# Harness_Wrapper.net
KiCad netlist of a schematic drawn in Altium Designer
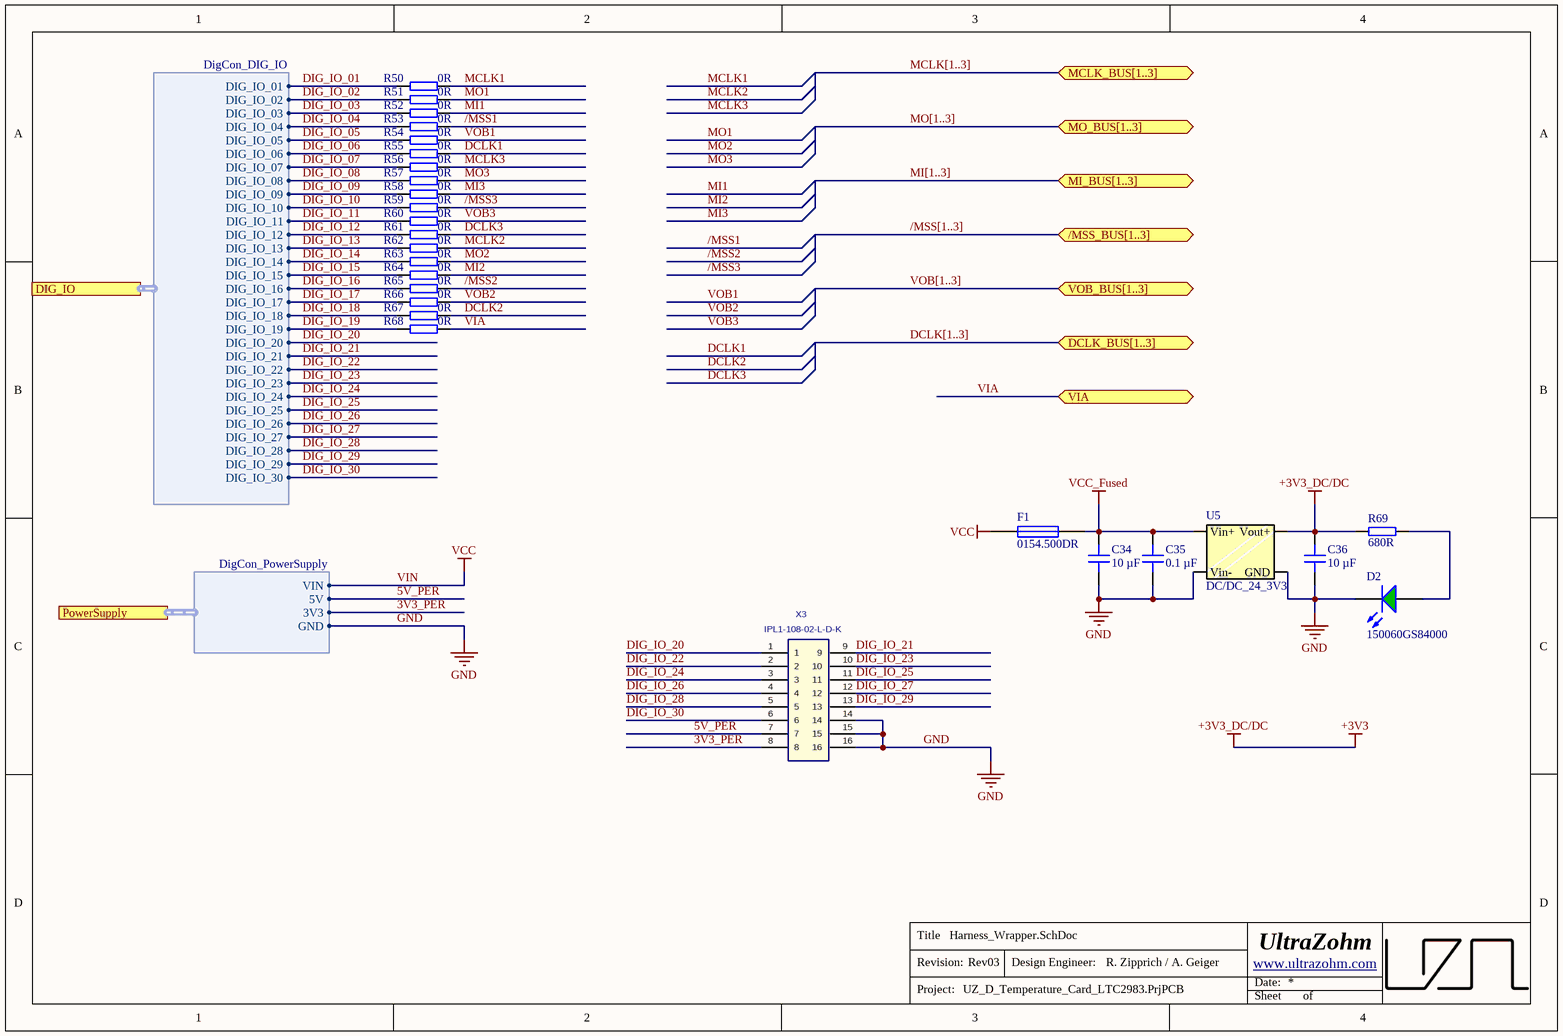
[diagram p0: Harness_Wrapper.SchDoc]

(export (version "E")
  (design (tool "Eeschema 10.0.6"))
  (components
    (comp (ref "C34")
      (value "10 µF")
      (footprint "C_0603")
      (description "Capacitor 0603, 6.3 VDC, 10 µF, X5R")
      (fields
        (field (name "MANUFACTURER PART NUMBER") "GRM185R60J106ME15D")
        (field (name "MANUFACTURER") "muRata")
        (field (name "CREATED FROM") "MGremer")
      )
      (libsource (lib "user") (part "Capacitor"))
    )
    (comp (ref "C35")
      (value "0.1 µF")
      (footprint "C_0603")
      (description "Capacitor 0603, 50 VDC, 0.1 µF, X7R")
      (fields
        (field (name "MANUFACTURER PART NUMBER") "C0603X104K5RAC7411")
        (field (name "MANUFACTURER") "KEMET")
        (field (name "CREATED FROM") "MGremer")
      )
      (libsource (lib "user") (part "Capacitor"))
    )
    (comp (ref "C36")
      (value "10 µF")
      (footprint "C_0603")
      (description "Capacitor 0603, 6.3 VDC, 10 µF, X5R")
      (fields
        (field (name "MANUFACTURER PART NUMBER") "GRM185R60J106ME15D")
        (field (name "MANUFACTURER") "muRata")
        (field (name "CREATED FROM") "MGremer")
      )
      (libsource (lib "user") (part "Capacitor"))
    )
    (comp (ref "D2")
      (value "150060GS84000")
      (footprint "WL-SMCW_0603")
      (description "WL-SMCW SMD Mono-color Chip LED Waterclear Green")
      (fields
        (field (name "MANUFACTURER") "Wuerth Elektronik")
        (field (name "LCSC PART NUMBER") "C72043")
        (field (name "CREATED FROM") "MGremer")
      )
      (libsource (lib "user") (part "LED_Green"))
    )
    (comp (ref "F1")
      (value "0154.500DR")
      (footprint "Littlefuse_154")
      (description "Fuse OMNI BLOK 154")
      (fields
        (field (name "MANUFACTURER") "Littlefuse")
        (field (name "LCSC PART NUMBER") "C720204")
        (field (name "CREATED FROM") "MGremer")
      )
      (libsource (lib "user") (part "Fuse Littelfuse 154 Fuse"))
    )
    (comp (ref "R50")
      (value "0R")
      (footprint "RES 0603_1608")
      (description "SMD resistor E24 series")
      (fields
        (field (name "MANUFACTURER PART NUMBER") "RC0603JR-070RL")
        (field (name "MANUFACTURER") "YAGEO")
        (field (name "CREATED FROM") "MGremer")
      )
      (libsource (lib "user") (part "Resistor"))
    )
    (comp (ref "R51")
      (value "0R")
      (footprint "RES 0603_1608")
      (description "SMD resistor E24 series")
      (fields
        (field (name "MANUFACTURER PART NUMBER") "RC0603JR-070RL")
        (field (name "MANUFACTURER") "YAGEO")
        (field (name "CREATED FROM") "MGremer")
      )
      (libsource (lib "user") (part "Resistor"))
    )
    (comp (ref "R52")
      (value "0R")
      (footprint "RES 0603_1608")
      (description "SMD resistor E24 series")
      (fields
        (field (name "MANUFACTURER PART NUMBER") "RC0603JR-070RL")
        (field (name "MANUFACTURER") "YAGEO")
        (field (name "CREATED FROM") "MGremer")
      )
      (libsource (lib "user") (part "Resistor"))
    )
    (comp (ref "R53")
      (value "0R")
      (footprint "RES 0603_1608")
      (description "SMD resistor E24 series")
      (fields
        (field (name "MANUFACTURER PART NUMBER") "RC0603JR-070RL")
        (field (name "MANUFACTURER") "YAGEO")
        (field (name "CREATED FROM") "MGremer")
      )
      (libsource (lib "user") (part "Resistor"))
    )
    (comp (ref "R54")
      (value "0R")
      (footprint "RES 0603_1608")
      (description "SMD resistor E24 series")
      (fields
        (field (name "MANUFACTURER PART NUMBER") "RC0603JR-070RL")
        (field (name "MANUFACTURER") "YAGEO")
        (field (name "CREATED FROM") "MGremer")
      )
      (libsource (lib "user") (part "Resistor"))
    )
    (comp (ref "R55")
      (value "0R")
      (footprint "RES 0603_1608")
      (description "SMD resistor E24 series")
      (fields
        (field (name "MANUFACTURER PART NUMBER") "RC0603JR-070RL")
        (field (name "MANUFACTURER") "YAGEO")
        (field (name "CREATED FROM") "MGremer")
      )
      (libsource (lib "user") (part "Resistor"))
    )
    (comp (ref "R56")
      (value "0R")
      (footprint "RES 0603_1608")
      (description "SMD resistor E24 series")
      (fields
        (field (name "MANUFACTURER PART NUMBER") "RC0603JR-070RL")
        (field (name "MANUFACTURER") "YAGEO")
        (field (name "CREATED FROM") "MGremer")
      )
      (libsource (lib "user") (part "Resistor"))
    )
    (comp (ref "R57")
      (value "0R")
      (footprint "RES 0603_1608")
      (description "SMD resistor E24 series")
      (fields
        (field (name "MANUFACTURER PART NUMBER") "RC0603JR-070RL")
        (field (name "MANUFACTURER") "YAGEO")
        (field (name "CREATED FROM") "MGremer")
      )
      (libsource (lib "user") (part "Resistor"))
    )
    (comp (ref "R58")
      (value "0R")
      (footprint "RES 0603_1608")
      (description "SMD resistor E24 series")
      (fields
        (field (name "MANUFACTURER PART NUMBER") "RC0603JR-070RL")
        (field (name "MANUFACTURER") "YAGEO")
        (field (name "CREATED FROM") "MGremer")
      )
      (libsource (lib "user") (part "Resistor"))
    )
    (comp (ref "R59")
      (value "0R")
      (footprint "RES 0603_1608")
      (description "SMD resistor E24 series")
      (fields
        (field (name "MANUFACTURER PART NUMBER") "RC0603JR-070RL")
        (field (name "MANUFACTURER") "YAGEO")
        (field (name "CREATED FROM") "MGremer")
      )
      (libsource (lib "user") (part "Resistor"))
    )
    (comp (ref "R60")
      (value "0R")
      (footprint "RES 0603_1608")
      (description "SMD resistor E24 series")
      (fields
        (field (name "MANUFACTURER PART NUMBER") "RC0603JR-070RL")
        (field (name "MANUFACTURER") "YAGEO")
        (field (name "CREATED FROM") "MGremer")
      )
      (libsource (lib "user") (part "Resistor"))
    )
    (comp (ref "R61")
      (value "0R")
      (footprint "RES 0603_1608")
      (description "SMD resistor E24 series")
      (fields
        (field (name "MANUFACTURER PART NUMBER") "RC0603JR-070RL")
        (field (name "MANUFACTURER") "YAGEO")
        (field (name "CREATED FROM") "MGremer")
      )
      (libsource (lib "user") (part "Resistor"))
    )
    (comp (ref "R62")
      (value "0R")
      (footprint "RES 0603_1608")
      (description "SMD resistor E24 series")
      (fields
        (field (name "MANUFACTURER PART NUMBER") "RC0603JR-070RL")
        (field (name "MANUFACTURER") "YAGEO")
        (field (name "CREATED FROM") "MGremer")
      )
      (libsource (lib "user") (part "Resistor"))
    )
    (comp (ref "R63")
      (value "0R")
      (footprint "RES 0603_1608")
      (description "SMD resistor E24 series")
      (fields
        (field (name "MANUFACTURER PART NUMBER") "RC0603JR-070RL")
        (field (name "MANUFACTURER") "YAGEO")
        (field (name "CREATED FROM") "MGremer")
      )
      (libsource (lib "user") (part "Resistor"))
    )
    (comp (ref "R64")
      (value "0R")
      (footprint "RES 0603_1608")
      (description "SMD resistor E24 series")
      (fields
        (field (name "MANUFACTURER PART NUMBER") "RC0603JR-070RL")
        (field (name "MANUFACTURER") "YAGEO")
        (field (name "CREATED FROM") "MGremer")
      )
      (libsource (lib "user") (part "Resistor"))
    )
    (comp (ref "R65")
      (value "0R")
      (footprint "RES 0603_1608")
      (description "SMD resistor E24 series")
      (fields
        (field (name "MANUFACTURER PART NUMBER") "RC0603JR-070RL")
        (field (name "MANUFACTURER") "YAGEO")
        (field (name "CREATED FROM") "MGremer")
      )
      (libsource (lib "user") (part "Resistor"))
    )
    (comp (ref "R66")
      (value "0R")
      (footprint "RES 0603_1608")
      (description "SMD resistor E24 series")
      (fields
        (field (name "MANUFACTURER PART NUMBER") "RC0603JR-070RL")
        (field (name "MANUFACTURER") "YAGEO")
        (field (name "CREATED FROM") "MGremer")
      )
      (libsource (lib "user") (part "Resistor"))
    )
    (comp (ref "R67")
      (value "0R")
      (footprint "RES 0603_1608")
      (description "SMD resistor E24 series")
      (fields
        (field (name "MANUFACTURER PART NUMBER") "RC0603JR-070RL")
        (field (name "MANUFACTURER") "YAGEO")
        (field (name "CREATED FROM") "MGremer")
      )
      (libsource (lib "user") (part "Resistor"))
    )
    (comp (ref "R68")
      (value "0R")
      (footprint "RES 0603_1608")
      (description "SMD resistor E24 series")
      (fields
        (field (name "MANUFACTURER PART NUMBER") "RC0603JR-070RL")
        (field (name "MANUFACTURER") "YAGEO")
        (field (name "CREATED FROM") "MGremer")
      )
      (libsource (lib "user") (part "Resistor"))
    )
    (comp (ref "R69")
      (value "680R")
      (footprint "RES 0603_1608")
      (description "SMD resistor E24 series")
      (fields
        (field (name "MANUFACTURER PART NUMBER") "RK73B1JTTDD681J")
        (field (name "MANUFACTURER") "KOA Speer")
        (field (name "CREATED FROM") "MGremer")
      )
      (libsource (lib "user") (part "Resistor"))
    )
    (comp (ref "U5")
      (value "DC/DC_24_3V3")
      (footprint "SIP4DCDC")
      (fields (field (name "LCSC PART NUMBER") "C7500913"))
      (libsource (lib "PRJ_LIB_LTC2983_Card") (part "DC/DC_Single"))
    )
    (comp (ref "X3")
      (value "IPL1-108-02-L-D-K")
      (footprint "IPL1-108-02-L-D-K")
      (description "2.54 mm Double Row Termin Assembly (SMD)")
      (fields (field (name "MANUFACTURER") "SAMTEC") (field (name "CREATED FROM") "MGremer"))
      (libsource (lib "user") (part "IPL1-108-XX-X-D-X"))
    )
  )
  (nets
    (net (code "6") (name "+3V3") (class "Default")
      (node (ref "C36") (pin "2") (pinfunction "2_2") (pintype "passive"))
      (node (ref "R69") (pin "1") (pinfunction "1_1") (pintype "passive"))
      (node (ref "U5") (pin "6") (pinfunction "Vout+_6") (pintype "passive"))
    )
    (net (code "7") (name "/3V3_PER") (class "Default")
      (node (ref "X3") (pin "8") (pinfunction "8_8") (pintype "passive"))
    )
    (net (code "8") (name "/5V_PER") (class "Default")
      (node (ref "X3") (pin "7") (pinfunction "7_7") (pintype "passive"))
    )
    (net (code "9") (name "/DCLK1") (class "Default")
      (node (ref "R55") (pin "2") (pinfunction "2_2") (pintype "passive"))
    )
    (net (code "10") (name "/DCLK2") (class "Default")
      (node (ref "R67") (pin "2") (pinfunction "2_2") (pintype "passive"))
    )
    (net (code "11") (name "/DCLK3") (class "Default")
      (node (ref "R61") (pin "2") (pinfunction "2_2") (pintype "passive"))
    )
    (net (code "13") (name "/DIG_IO_01") (class "Default")
      (node (ref "R50") (pin "1") (pinfunction "1_1") (pintype "passive"))
    )
    (net (code "14") (name "/DIG_IO_02") (class "Default")
      (node (ref "R51") (pin "1") (pinfunction "1_1") (pintype "passive"))
    )
    (net (code "15") (name "/DIG_IO_03") (class "Default")
      (node (ref "R52") (pin "1") (pinfunction "1_1") (pintype "passive"))
    )
    (net (code "16") (name "/DIG_IO_04") (class "Default")
      (node (ref "R53") (pin "1") (pinfunction "1_1") (pintype "passive"))
    )
    (net (code "17") (name "/DIG_IO_05") (class "Default")
      (node (ref "R54") (pin "1") (pinfunction "1_1") (pintype "passive"))
    )
    (net (code "18") (name "/DIG_IO_06") (class "Default")
      (node (ref "R55") (pin "1") (pinfunction "1_1") (pintype "passive"))
    )
    (net (code "19") (name "/DIG_IO_07") (class "Default")
      (node (ref "R56") (pin "1") (pinfunction "1_1") (pintype "passive"))
    )
    (net (code "20") (name "/DIG_IO_08") (class "Default")
      (node (ref "R57") (pin "1") (pinfunction "1_1") (pintype "passive"))
    )
    (net (code "21") (name "/DIG_IO_09") (class "Default")
      (node (ref "R58") (pin "1") (pinfunction "1_1") (pintype "passive"))
    )
    (net (code "22") (name "/DIG_IO_10") (class "Default")
      (node (ref "R59") (pin "1") (pinfunction "1_1") (pintype "passive"))
    )
    (net (code "23") (name "/DIG_IO_11") (class "Default")
      (node (ref "R60") (pin "1") (pinfunction "1_1") (pintype "passive"))
    )
    (net (code "24") (name "/DIG_IO_12") (class "Default")
      (node (ref "R61") (pin "1") (pinfunction "1_1") (pintype "passive"))
    )
    (net (code "25") (name "/DIG_IO_13") (class "Default")
      (node (ref "R62") (pin "1") (pinfunction "1_1") (pintype "passive"))
    )
    (net (code "26") (name "/DIG_IO_14") (class "Default")
      (node (ref "R63") (pin "1") (pinfunction "1_1") (pintype "passive"))
    )
    (net (code "27") (name "/DIG_IO_15") (class "Default")
      (node (ref "R64") (pin "1") (pinfunction "1_1") (pintype "passive"))
    )
    (net (code "28") (name "/DIG_IO_16") (class "Default")
      (node (ref "R65") (pin "1") (pinfunction "1_1") (pintype "passive"))
    )
    (net (code "29") (name "/DIG_IO_17") (class "Default")
      (node (ref "R66") (pin "1") (pinfunction "1_1") (pintype "passive"))
    )
    (net (code "30") (name "/DIG_IO_18") (class "Default")
      (node (ref "R67") (pin "1") (pinfunction "1_1") (pintype "passive"))
    )
    (net (code "31") (name "/DIG_IO_19") (class "Default")
      (node (ref "R68") (pin "1") (pinfunction "1_1") (pintype "passive"))
    )
    (net (code "32") (name "/DIG_IO_20") (class "Default")
      (node (ref "X3") (pin "1") (pinfunction "1_1") (pintype "passive"))
    )
    (net (code "33") (name "/DIG_IO_21") (class "Default")
      (node (ref "X3") (pin "9") (pinfunction "9_9") (pintype "passive"))
    )
    (net (code "34") (name "/DIG_IO_22") (class "Default")
      (node (ref "X3") (pin "2") (pinfunction "2_2") (pintype "passive"))
    )
    (net (code "35") (name "/DIG_IO_23") (class "Default")
      (node (ref "X3") (pin "10") (pinfunction "10_10") (pintype "passive"))
    )
    (net (code "36") (name "/DIG_IO_24") (class "Default")
      (node (ref "X3") (pin "3") (pinfunction "3_3") (pintype "passive"))
    )
    (net (code "37") (name "/DIG_IO_25") (class "Default")
      (node (ref "X3") (pin "11") (pinfunction "11_11") (pintype "passive"))
    )
    (net (code "38") (name "/DIG_IO_26") (class "Default")
      (node (ref "X3") (pin "4") (pinfunction "4_4") (pintype "passive"))
    )
    (net (code "39") (name "/DIG_IO_27") (class "Default")
      (node (ref "X3") (pin "12") (pinfunction "12_12") (pintype "passive"))
    )
    (net (code "40") (name "/DIG_IO_28") (class "Default")
      (node (ref "X3") (pin "5") (pinfunction "5_5") (pintype "passive"))
    )
    (net (code "41") (name "/DIG_IO_29") (class "Default")
      (node (ref "X3") (pin "13") (pinfunction "13_13") (pintype "passive"))
    )
    (net (code "42") (name "/DIG_IO_30") (class "Default")
      (node (ref "X3") (pin "6") (pinfunction "6_6") (pintype "passive"))
    )
    (net (code "43") (name "/MCLK1") (class "Default")
      (node (ref "R50") (pin "2") (pinfunction "2_2") (pintype "passive"))
    )
    (net (code "44") (name "/MCLK2") (class "Default")
      (node (ref "R62") (pin "2") (pinfunction "2_2") (pintype "passive"))
    )
    (net (code "45") (name "/MCLK3") (class "Default")
      (node (ref "R56") (pin "2") (pinfunction "2_2") (pintype "passive"))
    )
    (net (code "47") (name "/MI1") (class "Default")
      (node (ref "R52") (pin "2") (pinfunction "2_2") (pintype "passive"))
    )
    (net (code "48") (name "/MI2") (class "Default")
      (node (ref "R64") (pin "2") (pinfunction "2_2") (pintype "passive"))
    )
    (net (code "49") (name "/MI3") (class "Default")
      (node (ref "R58") (pin "2") (pinfunction "2_2") (pintype "passive"))
    )
    (net (code "51") (name "/MO1") (class "Default")
      (node (ref "R51") (pin "2") (pinfunction "2_2") (pintype "passive"))
    )
    (net (code "52") (name "/MO2") (class "Default")
      (node (ref "R63") (pin "2") (pinfunction "2_2") (pintype "passive"))
    )
    (net (code "53") (name "/MO3") (class "Default")
      (node (ref "R57") (pin "2") (pinfunction "2_2") (pintype "passive"))
    )
    (net (code "55") (name "/VIA") (class "Default")
      (node (ref "R68") (pin "2") (pinfunction "2_2") (pintype "passive"))
    )
    (net (code "56") (name "/VOB1") (class "Default")
      (node (ref "R54") (pin "2") (pinfunction "2_2") (pintype "passive"))
    )
    (net (code "57") (name "/VOB2") (class "Default")
      (node (ref "R66") (pin "2") (pinfunction "2_2") (pintype "passive"))
    )
    (net (code "58") (name "/VOB3") (class "Default")
      (node (ref "R60") (pin "2") (pinfunction "2_2") (pintype "passive"))
    )
    (net (code "62") (name "/{slash}MSS1") (class "Default")
      (node (ref "R53") (pin "2") (pinfunction "2_2") (pintype "passive"))
    )
    (net (code "63") (name "/{slash}MSS2") (class "Default")
      (node (ref "R65") (pin "2") (pinfunction "2_2") (pintype "passive"))
    )
    (net (code "64") (name "/{slash}MSS3") (class "Default")
      (node (ref "R59") (pin "2") (pinfunction "2_2") (pintype "passive"))
    )
    (net (code "66") (name "GND") (class "Default")
      (node (ref "C34") (pin "1") (pinfunction "1_1") (pintype "passive"))
      (node (ref "C35") (pin "1") (pinfunction "1_1") (pintype "passive"))
      (node (ref "C36") (pin "1") (pinfunction "1_1") (pintype "passive"))
      (node (ref "D2") (pin "1") (pinfunction "K_1") (pintype "passive"))
      (node (ref "U5") (pin "2") (pinfunction "Vin-_2") (pintype "passive"))
      (node (ref "U5") (pin "4") (pinfunction "GND_4") (pintype "passive"))
      (node (ref "X3") (pin "14") (pinfunction "14_14") (pintype "passive"))
      (node (ref "X3") (pin "15") (pinfunction "15_15") (pintype "passive"))
      (node (ref "X3") (pin "16") (pinfunction "16_16") (pintype "passive"))
    )
    (net (code "67") (name "Net-(D2-A)") (class "Default")
      (node (ref "D2") (pin "2") (pinfunction "A_2") (pintype "passive"))
      (node (ref "R69") (pin "2") (pinfunction "2_2") (pintype "passive"))
    )
    (net (code "68") (name "VCC") (class "Default")
      (node (ref "F1") (pin "1") (pinfunction "1_1") (pintype "passive"))
    )
    (net (code "69") (name "VCC_Fused") (class "Default")
      (node (ref "C34") (pin "2") (pinfunction "2_2") (pintype "passive"))
      (node (ref "C35") (pin "2") (pinfunction "2_2") (pintype "passive"))
      (node (ref "F1") (pin "2") (pinfunction "2_2") (pintype "passive"))
      (node (ref "U5") (pin "1") (pinfunction "Vin+_1") (pintype "passive"))
    )
  )
)
